# comms_sys_schematic.net
KiCad netlist of a schematic drawn in EAGLE
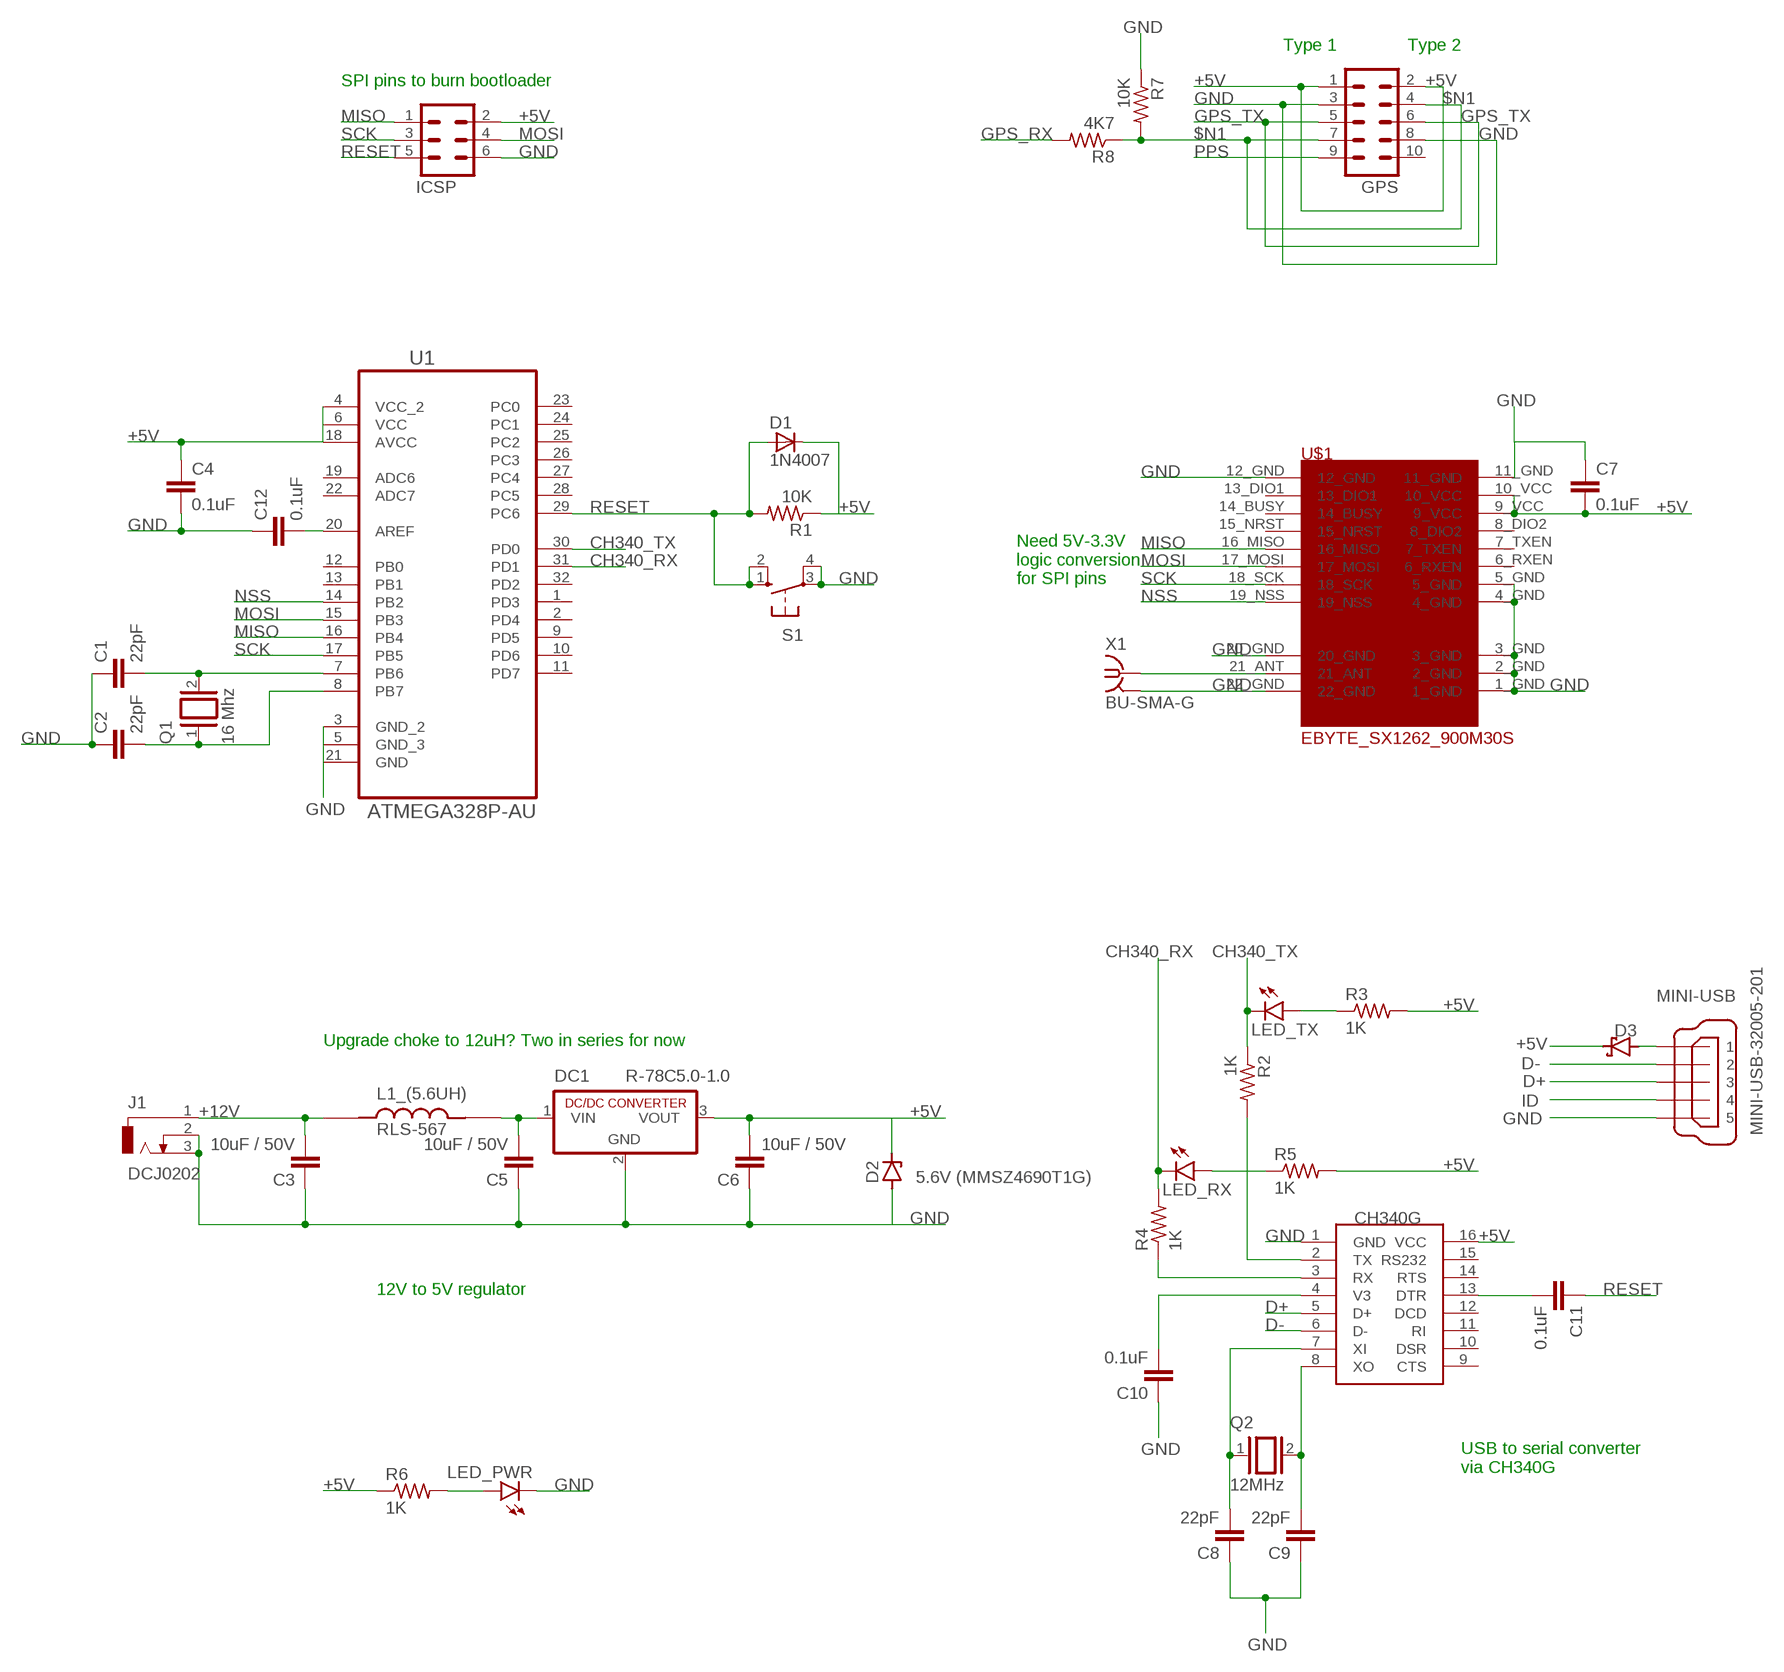
[diagram p0: schematic, sheet 1]

(export (version "E")
  (design (tool "Eeschema 10.0.6"))
  (components
    (comp (ref "C1")
      (value "22pF")
      (footprint "eagle-import:C2.5-3")
      (libsource (lib "eagle-import") (part "C2,5-3"))
    )
    (comp (ref "C2")
      (value "22pF")
      (footprint "eagle-import:C2.5-3")
      (libsource (lib "eagle-import") (part "C2,5-3"))
    )
    (comp (ref "C3")
      (value "10uF / 50V")
      (footprint "eagle-import:C2.5-3")
      (libsource (lib "eagle-import") (part "C2,5-3"))
    )
    (comp (ref "C4")
      (value "0.1uF")
      (footprint "eagle-import:C2.5-3")
      (libsource (lib "eagle-import") (part "C2,5-3"))
    )
    (comp (ref "C5")
      (value "10uF / 50V")
      (footprint "eagle-import:C2.5-3")
      (libsource (lib "eagle-import") (part "C2,5-3"))
    )
    (comp (ref "C6")
      (value "10uF / 50V")
      (footprint "eagle-import:C2.5-3")
      (libsource (lib "eagle-import") (part "C2,5-3"))
    )
    (comp (ref "C7")
      (value "0.1uF")
      (footprint "eagle-import:C2.5-3")
      (libsource (lib "eagle-import") (part "C2,5-3"))
    )
    (comp (ref "C8")
      (value "22pF")
      (footprint "eagle-import:C2.5-3")
      (libsource (lib "eagle-import") (part "C2,5-3"))
    )
    (comp (ref "C9")
      (value "22pF")
      (footprint "eagle-import:C2.5-3")
      (libsource (lib "eagle-import") (part "C2,5-3"))
    )
    (comp (ref "C10")
      (value "0.1uF")
      (footprint "eagle-import:C2.5-3")
      (libsource (lib "eagle-import") (part "C2,5-3"))
    )
    (comp (ref "C11")
      (value "0.1uF")
      (footprint "eagle-import:C2.5-3")
      (libsource (lib "eagle-import") (part "C2,5-3"))
    )
    (comp (ref "C12")
      (value "0.1uF")
      (footprint "eagle-import:C2.5-3")
      (libsource (lib "eagle-import") (part "C2,5-3"))
    )
    (comp (ref "D1")
      (value "1N4007")
      (footprint "eagle-import:SMA")
      (libsource (lib "eagle-import") (part "1N4007"))
    )
    (comp (ref "D2")
      (value "5.6V (MMSZ4690T1G)")
      (footprint "eagle-import:DO41Z10")
      (libsource (lib "eagle-import") (part "ZENER-DIODEDO41Z10"))
    )
    (comp (ref "D3")
      (value "SCHOTTKY-DIODESMD")
      (footprint "eagle-import:SMB")
      (libsource (lib "eagle-import") (part "SCHOTTKY-DIODESMD"))
    )
    (comp (ref "DC1")
      (value "R-78C5.0-1.0")
      (footprint "eagle-import:SIP3")
      (libsource (lib "eagle-import") (part "R-78C-1.05.0"))
    )
    (comp (ref "GPS")
      (value "MA05-2")
      (footprint "eagle-import:MA05-2")
      (libsource (lib "eagle-import") (part "MA05-2"))
    )
    (comp (ref "ICSP")
      (value "MA03-2")
      (footprint "eagle-import:MA03-2")
      (libsource (lib "eagle-import") (part "MA03-2"))
    )
    (comp (ref "J1")
      (value "DCJ0202")
      (footprint "eagle-import:DCJ0202")
      (libsource (lib "eagle-import") (part "DCJ0202"))
    )
    (comp (ref "L1_(5.6UH)")
      (value "RLS-567")
      (footprint "eagle-import:IND_RLS-567")
      (fields (field (name "MF") "Recom Power"))
      (libsource (lib "eagle-import") (part "RLS-567"))
    )
    (comp (ref "LED_PWR")
      (value "LEDCHIP-LED0805")
      (footprint "eagle-import:CHIP-LED0805")
      (libsource (lib "eagle-import") (part "LEDCHIP-LED0805"))
    )
    (comp (ref "LED_RX")
      (value "LEDCHIP-LED0805")
      (footprint "eagle-import:CHIP-LED0805")
      (libsource (lib "eagle-import") (part "LEDCHIP-LED0805"))
    )
    (comp (ref "LED_TX")
      (value "LEDCHIP-LED0805")
      (footprint "eagle-import:CHIP-LED0805")
      (libsource (lib "eagle-import") (part "LEDCHIP-LED0805"))
    )
    (comp (ref "MINI-USB")
      (value "MINI-USB-32005-201")
      (footprint "eagle-import:32005-201")
      (libsource (lib "eagle-import") (part "MINI-USB-32005-201"))
    )
    (comp (ref "Q1")
      (value "16 Mhz")
      (footprint "eagle-import:QS")
      (libsource (lib "eagle-import") (part "XTAL/S"))
    )
    (comp (ref "Q2")
      (value "12MHz")
      (footprint "eagle-import:QS")
      (libsource (lib "eagle-import") (part "XTAL/S"))
    )
    (comp (ref "R1")
      (value "10K")
      (footprint "eagle-import:R0805")
      (libsource (lib "eagle-import") (part "R-US_R0805"))
    )
    (comp (ref "R2")
      (value "1K")
      (footprint "eagle-import:R0805")
      (libsource (lib "eagle-import") (part "R-US_R0805"))
    )
    (comp (ref "R3")
      (value "1K")
      (footprint "eagle-import:R0805")
      (libsource (lib "eagle-import") (part "R-US_R0805"))
    )
    (comp (ref "R4")
      (value "1K")
      (footprint "eagle-import:R0805")
      (libsource (lib "eagle-import") (part "R-US_R0805"))
    )
    (comp (ref "R5")
      (value "1K")
      (footprint "eagle-import:R0805")
      (libsource (lib "eagle-import") (part "R-US_R0805"))
    )
    (comp (ref "R6")
      (value "1K")
      (footprint "eagle-import:R0805")
      (libsource (lib "eagle-import") (part "R-US_R0805"))
    )
    (comp (ref "R7")
      (value "10K")
      (footprint "eagle-import:R0805")
      (libsource (lib "eagle-import") (part "R-US_R0805"))
    )
    (comp (ref "R8")
      (value "4K7")
      (footprint "eagle-import:R0805")
      (libsource (lib "eagle-import") (part "R-US_R0805"))
    )
    (comp (ref "S1")
      (value "10-XX")
      (footprint "eagle-import:B3F-10XX")
      (fields (field (name "MPN") "B3F-1000"))
      (libsource (lib "eagle-import") (part "10-XX"))
    )
    (comp (ref "U$1")
      (value "EBYTE_SX1262_900M30S")
      (footprint "eagle-import:EBYTE_SX1262_900M30S_FOOTPRINT")
      (libsource (lib "eagle-import") (part "EBYTE_SX1262_900M30S"))
    )
    (comp (ref "U$2")
      (value "CH340G")
      (footprint "eagle-import:SOIC16")
      (libsource (lib "eagle-import") (part "CH340G"))
    )
    (comp (ref "U1")
      (value "ATMEGA328P-AU")
      (footprint "eagle-import:QFP80P900X900X120-32N")
      (libsource (lib "eagle-import") (part "ATMEGA328P-AU"))
    )
    (comp (ref "X1")
      (value "BU-SMA-G")
      (footprint "eagle-import:BU-SMA-G")
      (libsource (lib "eagle-import") (part "BU-SMA-G"))
    )
  )
  (nets
    (net (code "1") (name "/$N1") (class "Default")
      (node (ref "GPS") (pin "4") (pinfunction "4_4") (pintype "passive"))
      (node (ref "GPS") (pin "7") (pinfunction "7_7") (pintype "passive"))
      (node (ref "R7") (pin "2") (pinfunction "2_2") (pintype "passive"))
      (node (ref "R8") (pin "1") (pinfunction "1_1") (pintype "passive"))
    )
    (net (code "2") (name "/+5V") (class "Default")
      (node (ref "C4") (pin "1") (pinfunction "1_1") (pintype "passive"))
      (node (ref "C6") (pin "2") (pinfunction "2_2") (pintype "passive"))
      (node (ref "C7") (pin "2") (pinfunction "2_2") (pintype "passive"))
      (node (ref "D1") (pin "K") (pinfunction "C_K") (pintype "passive"))
      (node (ref "D2") (pin "C") (pinfunction "C_C") (pintype "passive"))
      (node (ref "D3") (pin "C") (pinfunction "C_C") (pintype "passive"))
      (node (ref "DC1") (pin "3") (pinfunction "VOUT_3") (pintype "passive"))
      (node (ref "GPS") (pin "1") (pinfunction "1_1") (pintype "passive"))
      (node (ref "GPS") (pin "2") (pinfunction "2_2") (pintype "passive"))
      (node (ref "ICSP") (pin "2") (pinfunction "2_2") (pintype "passive"))
      (node (ref "R1") (pin "1") (pinfunction "1_1") (pintype "passive"))
      (node (ref "R3") (pin "2") (pinfunction "2_2") (pintype "passive"))
      (node (ref "R5") (pin "2") (pinfunction "2_2") (pintype "passive"))
      (node (ref "R6") (pin "1") (pinfunction "1_1") (pintype "passive"))
      (node (ref "U$1") (pin "10_VCC") (pinfunction "10_VCC_10_VCC") (pintype "power_in"))
      (node (ref "U$1") (pin "9_VCC") (pinfunction "9_VCC_9_VCC") (pintype "power_in"))
      (node (ref "U$2") (pin "16") (pinfunction "VCC_16") (pintype "bidirectional"))
      (node (ref "U1") (pin "18") (pinfunction "AVCC_18") (pintype "power_in"))
      (node (ref "U1") (pin "4") (pinfunction "VCC_2_4") (pintype "power_in"))
      (node (ref "U1") (pin "6") (pinfunction "VCC_6") (pintype "power_in"))
    )
    (net (code "3") (name "/+12V") (class "Default")
      (node (ref "C3") (pin "2") (pinfunction "2_2") (pintype "passive"))
      (node (ref "J1") (pin "1") (pinfunction "1_1") (pintype "passive"))
      (node (ref "L1_(5.6UH)") (pin "1") (pinfunction "1_1") (pintype "passive"))
    )
    (net (code "4") (name "/CH340_RX") (class "Default")
      (node (ref "LED_RX") (pin "C") (pinfunction "C_C") (pintype "passive"))
      (node (ref "R4") (pin "2") (pinfunction "2_2") (pintype "passive"))
      (node (ref "U1") (pin "31") (pinfunction "PD1_31") (pintype "bidirectional"))
    )
    (net (code "5") (name "/CH340_TX") (class "Default")
      (node (ref "LED_TX") (pin "C") (pinfunction "C_C") (pintype "passive"))
      (node (ref "R2") (pin "1") (pinfunction "1_1") (pintype "passive"))
      (node (ref "U1") (pin "30") (pinfunction "PD0_30") (pintype "bidirectional"))
    )
    (net (code "6") (name "/D+") (class "Default")
      (node (ref "MINI-USB") (pin "3") (pinfunction "3_3") (pintype "passive"))
      (node (ref "U$2") (pin "5") (pinfunction "D+_5") (pintype "bidirectional"))
    )
    (net (code "7") (name "/D-") (class "Default")
      (node (ref "MINI-USB") (pin "2") (pinfunction "2_2") (pintype "passive"))
      (node (ref "U$2") (pin "6") (pinfunction "D-_6") (pintype "bidirectional"))
    )
    (net (code "8") (name "/GND") (class "Default")
      (node (ref "C1") (pin "1") (pinfunction "1_1") (pintype "passive"))
      (node (ref "C10") (pin "1") (pinfunction "1_1") (pintype "passive"))
      (node (ref "C12") (pin "1") (pinfunction "1_1") (pintype "passive"))
      (node (ref "C2") (pin "1") (pinfunction "1_1") (pintype "passive"))
      (node (ref "C3") (pin "1") (pinfunction "1_1") (pintype "passive"))
      (node (ref "C4") (pin "2") (pinfunction "2_2") (pintype "passive"))
      (node (ref "C5") (pin "1") (pinfunction "1_1") (pintype "passive"))
      (node (ref "C6") (pin "1") (pinfunction "1_1") (pintype "passive"))
      (node (ref "C7") (pin "1") (pinfunction "1_1") (pintype "passive"))
      (node (ref "C8") (pin "1") (pinfunction "1_1") (pintype "passive"))
      (node (ref "C9") (pin "1") (pinfunction "1_1") (pintype "passive"))
      (node (ref "D2") (pin "A") (pinfunction "A_A") (pintype "passive"))
      (node (ref "DC1") (pin "2") (pinfunction "GND_2") (pintype "passive"))
      (node (ref "GPS") (pin "3") (pinfunction "3_3") (pintype "passive"))
      (node (ref "GPS") (pin "8") (pinfunction "8_8") (pintype "passive"))
      (node (ref "ICSP") (pin "6") (pinfunction "6_6") (pintype "passive"))
      (node (ref "J1") (pin "2") (pinfunction "2_2") (pintype "passive"))
      (node (ref "J1") (pin "3") (pinfunction "3_3") (pintype "passive"))
      (node (ref "LED_PWR") (pin "C") (pinfunction "C_C") (pintype "passive"))
      (node (ref "MINI-USB") (pin "5") (pinfunction "5_5") (pintype "passive"))
      (node (ref "R7") (pin "1") (pinfunction "1_1") (pintype "passive"))
      (node (ref "S1") (pin "3") (pinfunction "P_3") (pintype "passive"))
      (node (ref "S1") (pin "4") (pinfunction "P1_4") (pintype "passive"))
      (node (ref "U$1") (pin "11_GND") (pinfunction "11_GND_11_GND") (pintype "power_in"))
      (node (ref "U$1") (pin "12_GND") (pinfunction "12_GND_12_GND") (pintype "power_in"))
      (node (ref "U$1") (pin "1_GND") (pinfunction "1_GND_1_GND") (pintype "power_in"))
      (node (ref "U$1") (pin "20_GND") (pinfunction "20_GND_20_GND") (pintype "power_in"))
      (node (ref "U$1") (pin "22_GND") (pinfunction "22_GND_22_GND") (pintype "power_in"))
      (node (ref "U$1") (pin "2_GND") (pinfunction "2_GND_2_GND") (pintype "power_in"))
      (node (ref "U$1") (pin "3_GND") (pinfunction "3_GND_3_GND") (pintype "power_in"))
      (node (ref "U$1") (pin "4_GND") (pinfunction "4_GND_4_GND") (pintype "power_in"))
      (node (ref "U$1") (pin "5_GND") (pinfunction "5_GND_5_GND") (pintype "power_in"))
      (node (ref "U$2") (pin "1") (pinfunction "GND_1") (pintype "bidirectional"))
      (node (ref "U1") (pin "21") (pinfunction "GND_21") (pintype "passive"))
      (node (ref "U1") (pin "3") (pinfunction "GND_2_3") (pintype "passive"))
      (node (ref "U1") (pin "5") (pinfunction "GND_3_5") (pintype "passive"))
      (node (ref "X1") (pin "2") (pinfunction "2_2") (pintype "passive"))
      (node (ref "X1") (pin "3") (pinfunction "2_3") (pintype "passive"))
      (node (ref "X1") (pin "4") (pinfunction "2_4") (pintype "passive"))
      (node (ref "X1") (pin "5") (pinfunction "2_5") (pintype "passive"))
    )
    (net (code "9") (name "/GPS_RX") (class "Default")
      (node (ref "R8") (pin "2") (pinfunction "2_2") (pintype "passive"))
    )
    (net (code "10") (name "/GPS_TX") (class "Default")
      (node (ref "GPS") (pin "5") (pinfunction "5_5") (pintype "passive"))
      (node (ref "GPS") (pin "6") (pinfunction "6_6") (pintype "passive"))
    )
    (net (code "11") (name "/ID") (class "Default")
      (node (ref "MINI-USB") (pin "4") (pinfunction "4_4") (pintype "passive"))
    )
    (net (code "12") (name "/MISO") (class "Default")
      (node (ref "ICSP") (pin "1") (pinfunction "1_1") (pintype "passive"))
      (node (ref "U$1") (pin "16_MISO") (pinfunction "16_MISO_16_MISO") (pintype "bidirectional"))
      (node (ref "U1") (pin "16") (pinfunction "PB4_16") (pintype "bidirectional"))
    )
    (net (code "13") (name "/MOSI") (class "Default")
      (node (ref "ICSP") (pin "4") (pinfunction "4_4") (pintype "passive"))
      (node (ref "U$1") (pin "17_MOSI") (pinfunction "17_MOSI_17_MOSI") (pintype "bidirectional"))
      (node (ref "U1") (pin "15") (pinfunction "PB3_15") (pintype "bidirectional"))
    )
    (net (code "14") (name "/NSS") (class "Default")
      (node (ref "U$1") (pin "19_NSS") (pinfunction "19_NSS_19_NSS") (pintype "bidirectional"))
      (node (ref "U1") (pin "14") (pinfunction "PB2_14") (pintype "bidirectional"))
    )
    (net (code "15") (name "/PPS") (class "Default")
      (node (ref "GPS") (pin "9") (pinfunction "9_9") (pintype "passive"))
    )
    (net (code "16") (name "/RESET") (class "Default")
      (node (ref "C11") (pin "1") (pinfunction "1_1") (pintype "passive"))
      (node (ref "D1") (pin "A") (pinfunction "A_A") (pintype "passive"))
      (node (ref "ICSP") (pin "5") (pinfunction "5_5") (pintype "passive"))
      (node (ref "R1") (pin "2") (pinfunction "2_2") (pintype "passive"))
      (node (ref "S1") (pin "1") (pinfunction "S_1") (pintype "passive"))
      (node (ref "S1") (pin "2") (pinfunction "S1_2") (pintype "passive"))
      (node (ref "U1") (pin "29") (pinfunction "PC6_29") (pintype "bidirectional"))
    )
    (net (code "17") (name "/SCK") (class "Default")
      (node (ref "ICSP") (pin "3") (pinfunction "3_3") (pintype "passive"))
      (node (ref "U$1") (pin "18_SCK") (pinfunction "18_SCK_18_SCK") (pintype "bidirectional"))
      (node (ref "U1") (pin "17") (pinfunction "PB5_17") (pintype "bidirectional"))
    )
    (net (code "18") (name "Net-(D3-PadA)") (class "Default")
      (node (ref "D3") (pin "A") (pinfunction "A_A") (pintype "passive"))
      (node (ref "MINI-USB") (pin "1") (pinfunction "1_1") (pintype "passive"))
    )
    (net (code "19") (name "Net-(DC1-VIN)") (class "Default")
      (node (ref "C5") (pin "2") (pinfunction "2_2") (pintype "passive"))
      (node (ref "DC1") (pin "1") (pinfunction "VIN_1") (pintype "passive"))
      (node (ref "L1_(5.6UH)") (pin "2") (pinfunction "2_2") (pintype "passive"))
    )
    (net (code "20") (name "Net-(LED_PWR-PadA)") (class "Default")
      (node (ref "LED_PWR") (pin "A") (pinfunction "A_A") (pintype "passive"))
      (node (ref "R6") (pin "2") (pinfunction "2_2") (pintype "passive"))
    )
    (net (code "21") (name "Net-(LED_RX-PadA)") (class "Default")
      (node (ref "LED_RX") (pin "A") (pinfunction "A_A") (pintype "passive"))
      (node (ref "R5") (pin "1") (pinfunction "1_1") (pintype "passive"))
    )
    (net (code "22") (name "Net-(LED_TX-PadA)") (class "Default")
      (node (ref "LED_TX") (pin "A") (pinfunction "A_A") (pintype "passive"))
      (node (ref "R3") (pin "1") (pinfunction "1_1") (pintype "passive"))
    )
    (net (code "23") (name "Net-(U$1-Pad21_ANT)") (class "Default")
      (node (ref "U$1") (pin "21_ANT") (pinfunction "21_ANT_21_ANT") (pintype "bidirectional"))
      (node (ref "X1") (pin "1") (pinfunction "1_1") (pintype "passive"))
    )
    (net (code "24") (name "Net-(U$2-DTR)") (class "Default")
      (node (ref "C11") (pin "2") (pinfunction "2_2") (pintype "passive"))
      (node (ref "U$2") (pin "13") (pinfunction "DTR_13") (pintype "bidirectional"))
    )
    (net (code "25") (name "Net-(U$2-RX)") (class "Default")
      (node (ref "R4") (pin "1") (pinfunction "1_1") (pintype "passive"))
      (node (ref "U$2") (pin "3") (pinfunction "RX_3") (pintype "bidirectional"))
    )
    (net (code "26") (name "Net-(U$2-TX)") (class "Default")
      (node (ref "R2") (pin "2") (pinfunction "2_2") (pintype "passive"))
      (node (ref "U$2") (pin "2") (pinfunction "TX_2") (pintype "bidirectional"))
    )
    (net (code "27") (name "Net-(U$2-V3)") (class "Default")
      (node (ref "C10") (pin "2") (pinfunction "2_2") (pintype "passive"))
      (node (ref "U$2") (pin "4") (pinfunction "V3_4") (pintype "bidirectional"))
    )
    (net (code "28") (name "Net-(U$2-XI)") (class "Default")
      (node (ref "C8") (pin "2") (pinfunction "2_2") (pintype "passive"))
      (node (ref "Q2") (pin "1") (pinfunction "1_1") (pintype "passive"))
      (node (ref "U$2") (pin "7") (pinfunction "XI_7") (pintype "bidirectional"))
    )
    (net (code "29") (name "Net-(U$2-XO)") (class "Default")
      (node (ref "C9") (pin "2") (pinfunction "2_2") (pintype "passive"))
      (node (ref "Q2") (pin "2") (pinfunction "2_2") (pintype "passive"))
      (node (ref "U$2") (pin "8") (pinfunction "XO_8") (pintype "bidirectional"))
    )
    (net (code "30") (name "Net-(U1-AREF)") (class "Default")
      (node (ref "C12") (pin "2") (pinfunction "2_2") (pintype "passive"))
      (node (ref "U1") (pin "20") (pinfunction "AREF_20") (pintype "input"))
    )
    (net (code "31") (name "Net-(U1-PB6)") (class "Default")
      (node (ref "C1") (pin "2") (pinfunction "2_2") (pintype "passive"))
      (node (ref "Q1") (pin "2") (pinfunction "2_2") (pintype "passive"))
      (node (ref "U1") (pin "7") (pinfunction "PB6_7") (pintype "bidirectional"))
    )
    (net (code "32") (name "Net-(U1-PB7)") (class "Default")
      (node (ref "C2") (pin "2") (pinfunction "2_2") (pintype "passive"))
      (node (ref "Q1") (pin "1") (pinfunction "1_1") (pintype "passive"))
      (node (ref "U1") (pin "8") (pinfunction "PB7_8") (pintype "bidirectional"))
    )
    (net (code "33") (name "unconnected-(GPS-Pad10)") (class "Default")
      (node (ref "GPS") (pin "10") (pinfunction "10_10") (pintype "passive"))
    )
    (net (code "34") (name "unconnected-(U$1-Pad6_RXEN)") (class "Default")
      (node (ref "U$1") (pin "6_RXEN") (pinfunction "6_RXEN_6_RXEN") (pintype "bidirectional"))
    )
    (net (code "35") (name "unconnected-(U$1-Pad7_TXEN)") (class "Default")
      (node (ref "U$1") (pin "7_TXEN") (pinfunction "7_TXEN_7_TXEN") (pintype "bidirectional"))
    )
    (net (code "36") (name "unconnected-(U$1-Pad8_DIO2)") (class "Default")
      (node (ref "U$1") (pin "8_DIO2") (pinfunction "8_DIO2_8_DIO2") (pintype "bidirectional"))
    )
    (net (code "37") (name "unconnected-(U$1-Pad13_DIO1)") (class "Default")
      (node (ref "U$1") (pin "13_DIO1") (pinfunction "13_DIO1_13_DIO1") (pintype "bidirectional"))
    )
    (net (code "38") (name "unconnected-(U$1-Pad14_BUSY)") (class "Default")
      (node (ref "U$1") (pin "14_BUSY") (pinfunction "14_BUSY_14_BUSY") (pintype "bidirectional"))
    )
    (net (code "39") (name "unconnected-(U$1-Pad15_NRST)") (class "Default")
      (node (ref "U$1") (pin "15_NRST") (pinfunction "15_NRST_15_NRST") (pintype "bidirectional"))
    )
    (net (code "40") (name "unconnected-(U$2-CTS-Pad9)") (class "Default")
      (node (ref "U$2") (pin "9") (pinfunction "CTS_9") (pintype "bidirectional"))
    )
    (net (code "41") (name "unconnected-(U$2-DCD-Pad12)") (class "Default")
      (node (ref "U$2") (pin "12") (pinfunction "DCD_12") (pintype "bidirectional"))
    )
    (net (code "42") (name "unconnected-(U$2-DSR-Pad10)") (class "Default")
      (node (ref "U$2") (pin "10") (pinfunction "DSR_10") (pintype "bidirectional"))
    )
    (net (code "43") (name "unconnected-(U$2-RI-Pad11)") (class "Default")
      (node (ref "U$2") (pin "11") (pinfunction "RI_11") (pintype "bidirectional"))
    )
    (net (code "44") (name "unconnected-(U$2-RS232-Pad15)") (class "Default")
      (node (ref "U$2") (pin "15") (pinfunction "RS232_15") (pintype "bidirectional"))
    )
    (net (code "45") (name "unconnected-(U$2-RTS-Pad14)") (class "Default")
      (node (ref "U$2") (pin "14") (pinfunction "RTS_14") (pintype "bidirectional"))
    )
    (net (code "46") (name "unconnected-(U1-ADC6-Pad19)") (class "Default")
      (node (ref "U1") (pin "19") (pinfunction "ADC6_19") (pintype "input"))
    )
    (net (code "47") (name "unconnected-(U1-ADC7-Pad22)") (class "Default")
      (node (ref "U1") (pin "22") (pinfunction "ADC7_22") (pintype "input"))
    )
    (net (code "48") (name "unconnected-(U1-PB0-Pad12)") (class "Default")
      (node (ref "U1") (pin "12") (pinfunction "PB0_12") (pintype "bidirectional"))
    )
    (net (code "49") (name "unconnected-(U1-PB1-Pad13)") (class "Default")
      (node (ref "U1") (pin "13") (pinfunction "PB1_13") (pintype "bidirectional"))
    )
    (net (code "50") (name "unconnected-(U1-PC0-Pad23)") (class "Default")
      (node (ref "U1") (pin "23") (pinfunction "PC0_23") (pintype "bidirectional"))
    )
    (net (code "51") (name "unconnected-(U1-PC1-Pad24)") (class "Default")
      (node (ref "U1") (pin "24") (pinfunction "PC1_24") (pintype "bidirectional"))
    )
    (net (code "52") (name "unconnected-(U1-PC2-Pad25)") (class "Default")
      (node (ref "U1") (pin "25") (pinfunction "PC2_25") (pintype "bidirectional"))
    )
    (net (code "53") (name "unconnected-(U1-PC3-Pad26)") (class "Default")
      (node (ref "U1") (pin "26") (pinfunction "PC3_26") (pintype "bidirectional"))
    )
    (net (code "54") (name "unconnected-(U1-PC4-Pad27)") (class "Default")
      (node (ref "U1") (pin "27") (pinfunction "PC4_27") (pintype "bidirectional"))
    )
    (net (code "55") (name "unconnected-(U1-PC5-Pad28)") (class "Default")
      (node (ref "U1") (pin "28") (pinfunction "PC5_28") (pintype "bidirectional"))
    )
    (net (code "56") (name "unconnected-(U1-PD2-Pad32)") (class "Default")
      (node (ref "U1") (pin "32") (pinfunction "PD2_32") (pintype "bidirectional"))
    )
    (net (code "57") (name "unconnected-(U1-PD3-Pad1)") (class "Default")
      (node (ref "U1") (pin "1") (pinfunction "PD3_1") (pintype "bidirectional"))
    )
    (net (code "58") (name "unconnected-(U1-PD4-Pad2)") (class "Default")
      (node (ref "U1") (pin "2") (pinfunction "PD4_2") (pintype "bidirectional"))
    )
    (net (code "59") (name "unconnected-(U1-PD5-Pad9)") (class "Default")
      (node (ref "U1") (pin "9") (pinfunction "PD5_9") (pintype "bidirectional"))
    )
    (net (code "60") (name "unconnected-(U1-PD6-Pad10)") (class "Default")
      (node (ref "U1") (pin "10") (pinfunction "PD6_10") (pintype "bidirectional"))
    )
    (net (code "61") (name "unconnected-(U1-PD7-Pad11)") (class "Default")
      (node (ref "U1") (pin "11") (pinfunction "PD7_11") (pintype "bidirectional"))
    )
  )
)
